# BatteryTemp.net
KiCad netlist of a schematic drawn in EAGLE
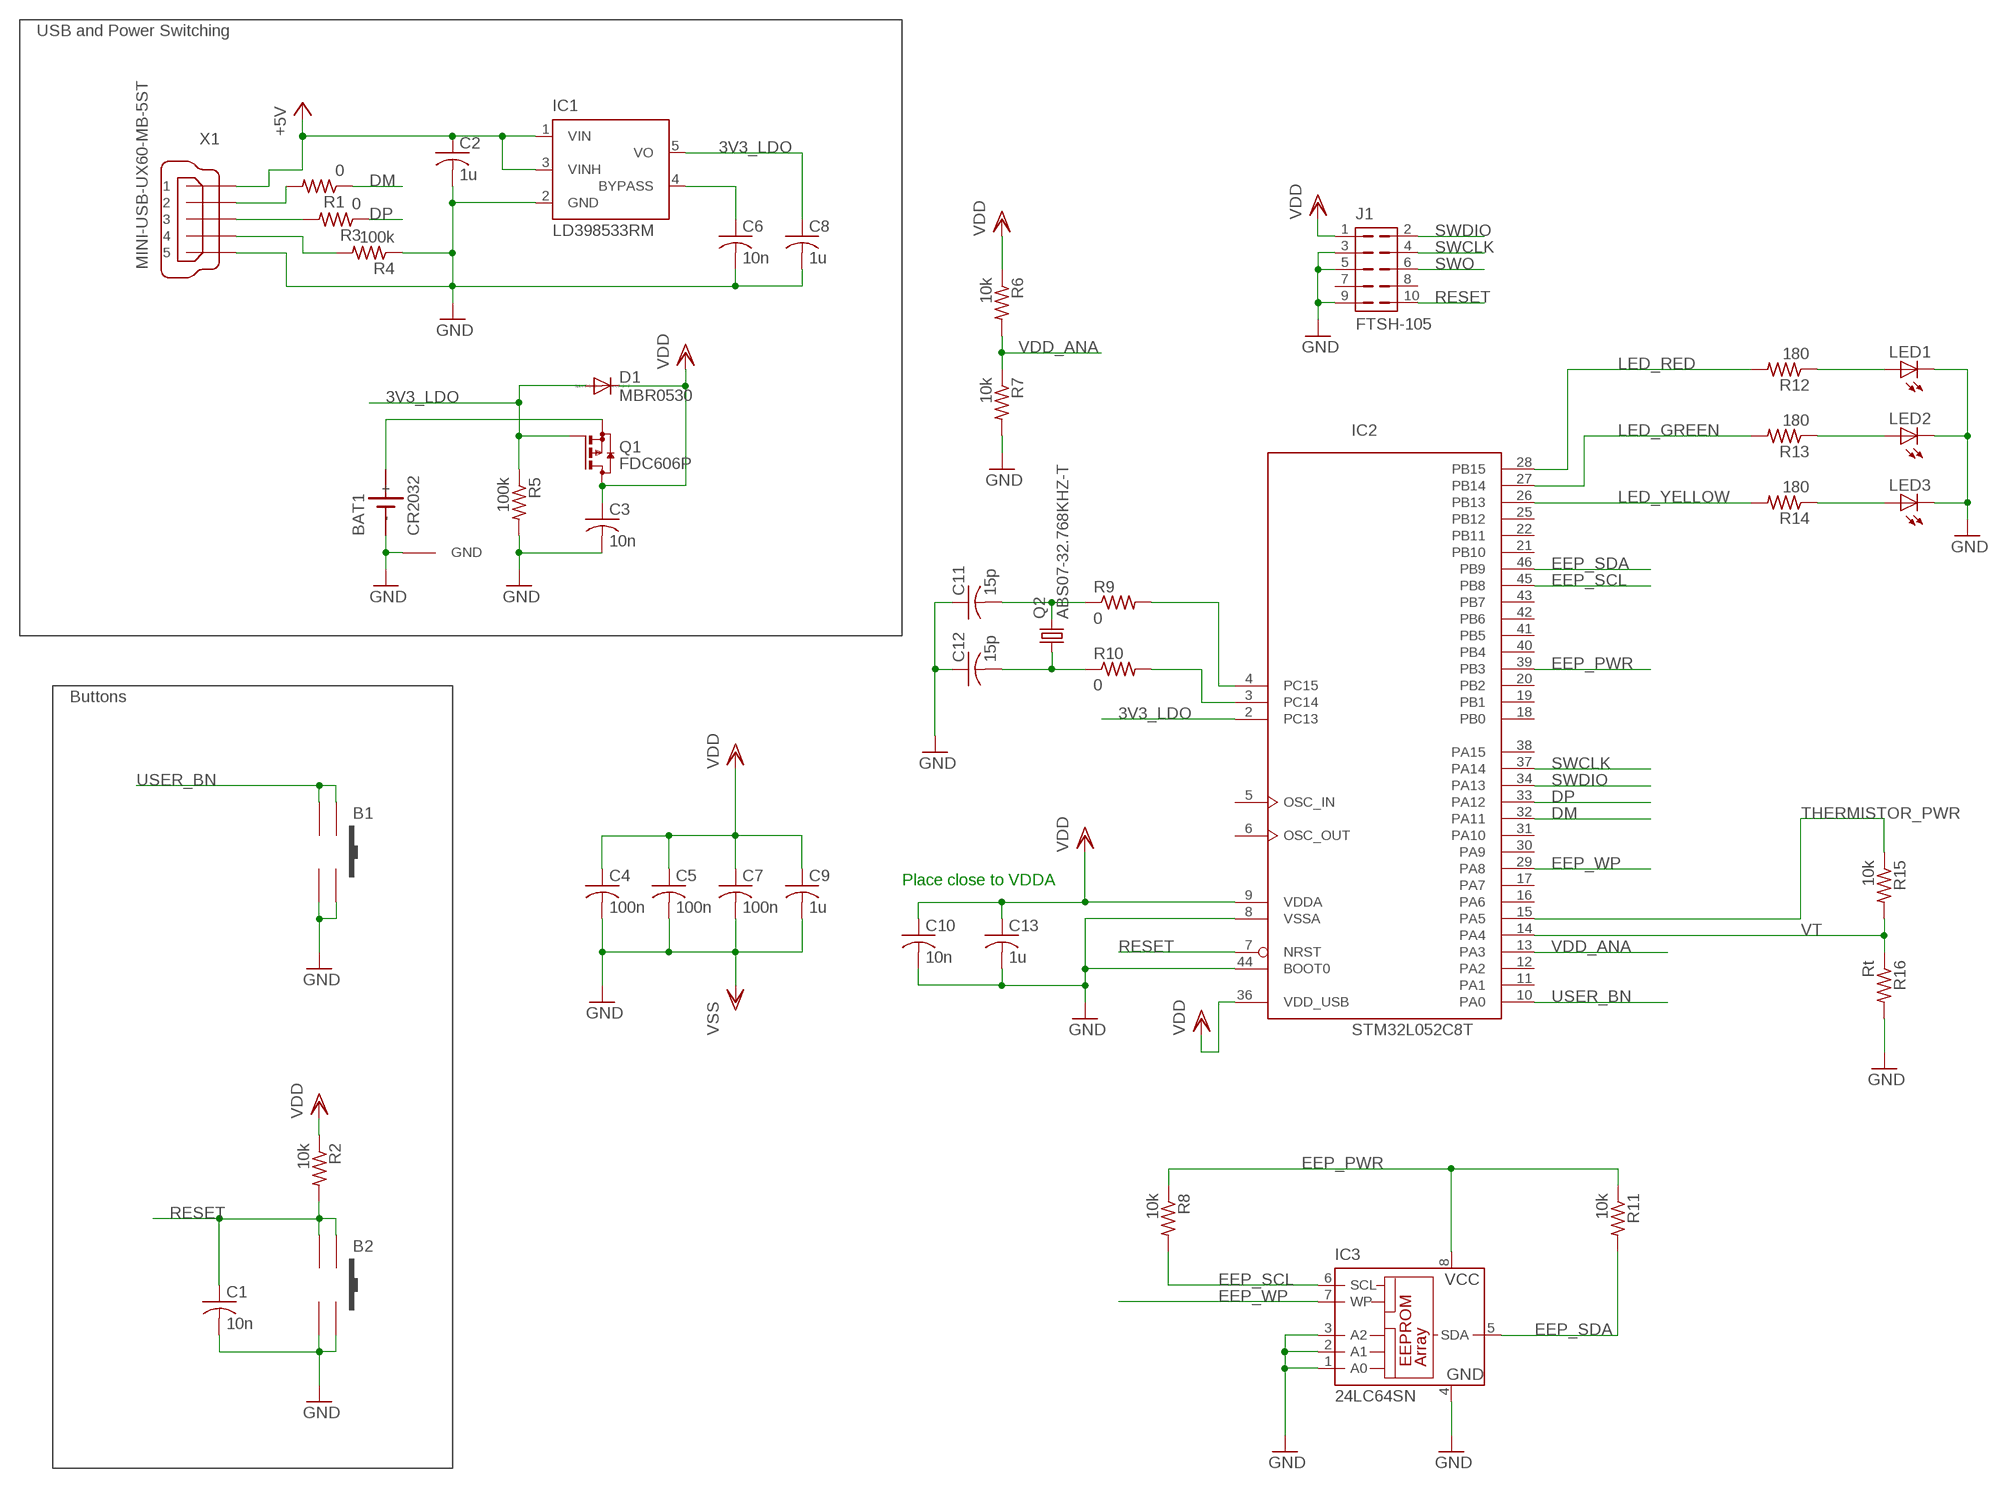
[diagram p0: schematic, sheet 1]

(export (version "E")
  (design (tool "Eeschema 10.0.6"))
  (components
    (comp (ref "B1")
      (value "PTS525SM10SMTR")
      (footprint "eagle-import:PTS525SM10SMTR")
      (libsource (lib "eagle-import") (part "PTS525SM10SMTR"))
    )
    (comp (ref "B2")
      (value "PTS525SM10SMTR")
      (footprint "eagle-import:PTS525SM10SMTR")
      (libsource (lib "eagle-import") (part "PTS525SM10SMTR"))
    )
    (comp (ref "BAT1")
      (value "CR2032")
      (footprint "eagle-import:COIN_CELL")
      (libsource (lib "eagle-import") (part "SN2032"))
    )
    (comp (ref "C1")
      (value "10n")
      (footprint "eagle-import:C0603")
      (libsource (lib "eagle-import") (part "C-USC0603"))
    )
    (comp (ref "C2")
      (value "1u")
      (footprint "eagle-import:C0603")
      (libsource (lib "eagle-import") (part "C-USC0603"))
    )
    (comp (ref "C3")
      (value "10n")
      (footprint "eagle-import:C0603")
      (libsource (lib "eagle-import") (part "C-USC0603"))
    )
    (comp (ref "C4")
      (value "100n")
      (footprint "eagle-import:C0603")
      (libsource (lib "eagle-import") (part "C-USC0603"))
    )
    (comp (ref "C5")
      (value "100n")
      (footprint "eagle-import:C0603")
      (libsource (lib "eagle-import") (part "C-USC0603"))
    )
    (comp (ref "C6")
      (value "10n")
      (footprint "eagle-import:C0603")
      (libsource (lib "eagle-import") (part "C-USC0603"))
    )
    (comp (ref "C7")
      (value "100n")
      (footprint "eagle-import:C0603")
      (libsource (lib "eagle-import") (part "C-USC0603"))
    )
    (comp (ref "C8")
      (value "1u")
      (footprint "eagle-import:C0603")
      (libsource (lib "eagle-import") (part "C-USC0603"))
    )
    (comp (ref "C9")
      (value "1u")
      (footprint "eagle-import:C0603")
      (libsource (lib "eagle-import") (part "C-USC0603"))
    )
    (comp (ref "C10")
      (value "10n")
      (footprint "eagle-import:C0603")
      (libsource (lib "eagle-import") (part "C-USC0603"))
    )
    (comp (ref "C11")
      (value "15p")
      (footprint "eagle-import:C0603")
      (libsource (lib "eagle-import") (part "C-USC0603"))
    )
    (comp (ref "C12")
      (value "15p")
      (footprint "eagle-import:C0603")
      (libsource (lib "eagle-import") (part "C-USC0603"))
    )
    (comp (ref "C13")
      (value "1u")
      (footprint "eagle-import:C0603")
      (libsource (lib "eagle-import") (part "C-USC0603"))
    )
    (comp (ref "D1")
      (value "MBR0530")
      (footprint "eagle-import:SOD-123_MINI-SMA")
      (libsource (lib "eagle-import") (part "CGRM400-G1"))
    )
    (comp (ref "IC1")
      (value "LD398533RM")
      (footprint "eagle-import:SOT23-5L")
      (libsource (lib "eagle-import") (part "LD3985M33R"))
    )
    (comp (ref "IC2")
      (value "STM32L052C8T")
      (footprint "eagle-import:LQFP48")
      (libsource (lib "eagle-import") (part "STM32L052CT8"))
    )
    (comp (ref "IC3")
      (value "24LC64SN")
      (footprint "eagle-import:SO-08")
      (fields (field (name "MF") "MICROCHIP") (field (name "MPN") "24LC64-I/SN"))
      (libsource (lib "eagle-import") (part "24SNLC64"))
    )
    (comp (ref "J1")
      (value "FTSH-105")
      (footprint "eagle-import:FTSH-105-01-XXX-DV-K")
      (libsource (lib "eagle-import") (part "FTSH-105"))
    )
    (comp (ref "LED1")
      (value "LEDCHIP-LED0603")
      (footprint "eagle-import:CHIP-LED0603")
      (libsource (lib "eagle-import") (part "LEDCHIP-LED0603"))
    )
    (comp (ref "LED2")
      (value "LEDCHIP-LED0603")
      (footprint "eagle-import:CHIP-LED0603")
      (libsource (lib "eagle-import") (part "LEDCHIP-LED0603"))
    )
    (comp (ref "LED3")
      (value "LEDCHIP-LED0603")
      (footprint "eagle-import:CHIP-LED0603")
      (libsource (lib "eagle-import") (part "LEDCHIP-LED0603"))
    )
    (comp (ref "Q1")
      (value "FDC606P")
      (footprint "eagle-import:SOT-23-6")
      (libsource (lib "eagle-import") (part "FDC606P"))
    )
    (comp (ref "Q2")
      (value "ABS07-32.768KHZ-T")
      (footprint "eagle-import:2-SMD")
      (libsource (lib "eagle-import") (part "ABS07-32.768KHZ-T"))
    )
    (comp (ref "R1")
      (value "0")
      (footprint "eagle-import:R0603")
      (libsource (lib "eagle-import") (part "R-US_R0603"))
    )
    (comp (ref "R2")
      (value "10k")
      (footprint "eagle-import:R0603")
      (libsource (lib "eagle-import") (part "R-US_R0603"))
    )
    (comp (ref "R3")
      (value "0")
      (footprint "eagle-import:R0603")
      (libsource (lib "eagle-import") (part "R-US_R0603"))
    )
    (comp (ref "R4")
      (value "100k")
      (footprint "eagle-import:R0603")
      (libsource (lib "eagle-import") (part "R-US_R0603"))
    )
    (comp (ref "R5")
      (value "100k")
      (footprint "eagle-import:R0603")
      (libsource (lib "eagle-import") (part "R-US_R0603"))
    )
    (comp (ref "R6")
      (value "10k")
      (footprint "eagle-import:R0603")
      (libsource (lib "eagle-import") (part "R-US_R0603"))
    )
    (comp (ref "R7")
      (value "10k")
      (footprint "eagle-import:R0603")
      (libsource (lib "eagle-import") (part "R-US_R0603"))
    )
    (comp (ref "R8")
      (value "10k")
      (footprint "eagle-import:R0603")
      (libsource (lib "eagle-import") (part "R-US_R0603"))
    )
    (comp (ref "R9")
      (value "0")
      (footprint "eagle-import:R0603")
      (libsource (lib "eagle-import") (part "R-US_R0603"))
    )
    (comp (ref "R10")
      (value "0")
      (footprint "eagle-import:R0603")
      (libsource (lib "eagle-import") (part "R-US_R0603"))
    )
    (comp (ref "R11")
      (value "10k")
      (footprint "eagle-import:R0603")
      (libsource (lib "eagle-import") (part "R-US_R0603"))
    )
    (comp (ref "R12")
      (value "180")
      (footprint "eagle-import:R0603")
      (libsource (lib "eagle-import") (part "R-US_R0603"))
    )
    (comp (ref "R13")
      (value "180")
      (footprint "eagle-import:R0603")
      (libsource (lib "eagle-import") (part "R-US_R0603"))
    )
    (comp (ref "R14")
      (value "180")
      (footprint "eagle-import:R0603")
      (libsource (lib "eagle-import") (part "R-US_R0603"))
    )
    (comp (ref "R15")
      (value "10k")
      (footprint "eagle-import:R0603")
      (libsource (lib "eagle-import") (part "R-US_R0603"))
    )
    (comp (ref "R16")
      (value "Rt")
      (footprint "eagle-import:R0603")
      (libsource (lib "eagle-import") (part "R-US_R0603"))
    )
    (comp (ref "T1")
      (value "GND_LUG")
      (footprint "eagle-import:GND_PAD")
      (libsource (lib "eagle-import") (part "GND_LUG"))
    )
    (comp (ref "X1")
      (value "MINI-USB-UX60-MB-5ST")
      (footprint "eagle-import:UX60-MB-5ST")
      (libsource (lib "eagle-import") (part "MINI-USB-UX60-MB-5ST"))
    )
  )
  (nets
    (net (code "1") (name "+5V") (class "Default")
      (node (ref "C2") (pin "1") (pinfunction "1_1") (pintype "passive"))
      (node (ref "IC1") (pin "1") (pinfunction "VIN_1") (pintype "input"))
      (node (ref "IC1") (pin "3") (pinfunction "VINH_3") (pintype "input"))
      (node (ref "X1") (pin "1") (pinfunction "1_1") (pintype "input"))
    )
    (net (code "2") (name "/3V3_LDO") (class "Default")
      (node (ref "C8") (pin "1") (pinfunction "1_1") (pintype "passive"))
      (node (ref "D1") (pin "A") (pinfunction "A_A") (pintype "passive"))
      (node (ref "IC1") (pin "5") (pinfunction "VO_5") (pintype "output"))
      (node (ref "IC2") (pin "2") (pinfunction "PC13_2") (pintype "bidirectional"))
      (node (ref "Q1") (pin "3") (pinfunction "G_3") (pintype "passive"))
      (node (ref "R5") (pin "1") (pinfunction "1_1") (pintype "passive"))
    )
    (net (code "3") (name "/DM") (class "Default")
      (node (ref "IC2") (pin "32") (pinfunction "PA11_32") (pintype "bidirectional"))
      (node (ref "R1") (pin "1") (pinfunction "1_1") (pintype "passive"))
    )
    (net (code "4") (name "/DP") (class "Default")
      (node (ref "IC2") (pin "33") (pinfunction "PA12_33") (pintype "bidirectional"))
      (node (ref "R3") (pin "1") (pinfunction "1_1") (pintype "passive"))
    )
    (net (code "5") (name "/EEP_PWR") (class "Default")
      (node (ref "IC2") (pin "39") (pinfunction "PB3_39") (pintype "bidirectional"))
      (node (ref "IC3") (pin "8") (pinfunction "VCC_8") (pintype "power_in"))
      (node (ref "R11") (pin "1") (pinfunction "1_1") (pintype "passive"))
      (node (ref "R8") (pin "1") (pinfunction "1_1") (pintype "passive"))
    )
    (net (code "6") (name "/EEP_SCL") (class "Default")
      (node (ref "IC2") (pin "45") (pinfunction "PB8_45") (pintype "bidirectional"))
      (node (ref "IC3") (pin "6") (pinfunction "SCL_6") (pintype "input"))
      (node (ref "R8") (pin "2") (pinfunction "2_2") (pintype "passive"))
    )
    (net (code "7") (name "/EEP_SDA") (class "Default")
      (node (ref "IC2") (pin "46") (pinfunction "PB9_46") (pintype "bidirectional"))
      (node (ref "IC3") (pin "5") (pinfunction "SDA_5") (pintype "bidirectional"))
      (node (ref "R11") (pin "2") (pinfunction "2_2") (pintype "passive"))
    )
    (net (code "8") (name "/EEP_WP") (class "Default")
      (node (ref "IC2") (pin "29") (pinfunction "PA8_29") (pintype "bidirectional"))
      (node (ref "IC3") (pin "7") (pinfunction "WP_7") (pintype "input"))
    )
    (net (code "9") (name "/LED_GREEN") (class "Default")
      (node (ref "IC2") (pin "27") (pinfunction "PB14_27") (pintype "bidirectional"))
      (node (ref "R13") (pin "2") (pinfunction "2_2") (pintype "passive"))
    )
    (net (code "10") (name "/LED_RED") (class "Default")
      (node (ref "IC2") (pin "28") (pinfunction "PB15_28") (pintype "bidirectional"))
      (node (ref "R12") (pin "2") (pinfunction "2_2") (pintype "passive"))
    )
    (net (code "11") (name "/LED_YELLOW") (class "Default")
      (node (ref "IC2") (pin "26") (pinfunction "PB13_26") (pintype "bidirectional"))
      (node (ref "R14") (pin "2") (pinfunction "2_2") (pintype "passive"))
    )
    (net (code "12") (name "/RESET") (class "Default")
      (node (ref "B2") (pin "1") (pinfunction "P1_1") (pintype "bidirectional"))
      (node (ref "B2") (pin "2") (pinfunction "P2_2") (pintype "bidirectional"))
      (node (ref "C1") (pin "1") (pinfunction "1_1") (pintype "passive"))
      (node (ref "IC2") (pin "7") (pinfunction "NRST_7") (pintype "bidirectional"))
      (node (ref "J1") (pin "10") (pinfunction "10_10") (pintype "passive"))
      (node (ref "R2") (pin "2") (pinfunction "2_2") (pintype "passive"))
    )
    (net (code "13") (name "/SWCLK") (class "Default")
      (node (ref "IC2") (pin "37") (pinfunction "PA14_37") (pintype "bidirectional"))
      (node (ref "J1") (pin "4") (pinfunction "4_4") (pintype "passive"))
    )
    (net (code "14") (name "/SWDIO") (class "Default")
      (node (ref "IC2") (pin "34") (pinfunction "PA13_34") (pintype "bidirectional"))
      (node (ref "J1") (pin "2") (pinfunction "2_2") (pintype "passive"))
    )
    (net (code "15") (name "/SWO") (class "Default")
      (node (ref "J1") (pin "6") (pinfunction "6_6") (pintype "passive"))
    )
    (net (code "16") (name "/THERMISTOR_PWR") (class "Default")
      (node (ref "IC2") (pin "15") (pinfunction "PA5_15") (pintype "bidirectional"))
      (node (ref "R15") (pin "1") (pinfunction "1_1") (pintype "passive"))
    )
    (net (code "17") (name "/USER_BN") (class "Default")
      (node (ref "B1") (pin "1") (pinfunction "P1_1") (pintype "bidirectional"))
      (node (ref "B1") (pin "2") (pinfunction "P2_2") (pintype "bidirectional"))
      (node (ref "IC2") (pin "10") (pinfunction "PA0_10") (pintype "bidirectional"))
    )
    (net (code "18") (name "/VDD_ANA") (class "Default")
      (node (ref "IC2") (pin "13") (pinfunction "PA3_13") (pintype "bidirectional"))
      (node (ref "R6") (pin "2") (pinfunction "2_2") (pintype "passive"))
      (node (ref "R7") (pin "1") (pinfunction "1_1") (pintype "passive"))
    )
    (net (code "19") (name "/VT") (class "Default")
      (node (ref "IC2") (pin "14") (pinfunction "PA4_14") (pintype "bidirectional"))
      (node (ref "R15") (pin "2") (pinfunction "2_2") (pintype "passive"))
      (node (ref "R16") (pin "1") (pinfunction "1_1") (pintype "passive"))
    )
    (net (code "20") (name "GND") (class "Default")
      (node (ref "B1") (pin "3") (pinfunction "P3_3") (pintype "bidirectional"))
      (node (ref "B1") (pin "4") (pinfunction "P4_4") (pintype "bidirectional"))
      (node (ref "B2") (pin "3") (pinfunction "P3_3") (pintype "bidirectional"))
      (node (ref "B2") (pin "4") (pinfunction "P4_4") (pintype "bidirectional"))
      (node (ref "BAT1") (pin "GND1") (pinfunction "-_GND1") (pintype "passive"))
      (node (ref "C1") (pin "2") (pinfunction "2_2") (pintype "passive"))
      (node (ref "C10") (pin "2") (pinfunction "2_2") (pintype "passive"))
      (node (ref "C11") (pin "1") (pinfunction "1_1") (pintype "passive"))
      (node (ref "C12") (pin "1") (pinfunction "1_1") (pintype "passive"))
      (node (ref "C13") (pin "2") (pinfunction "2_2") (pintype "passive"))
      (node (ref "C2") (pin "2") (pinfunction "2_2") (pintype "passive"))
      (node (ref "C3") (pin "2") (pinfunction "2_2") (pintype "passive"))
      (node (ref "C4") (pin "2") (pinfunction "2_2") (pintype "passive"))
      (node (ref "C5") (pin "2") (pinfunction "2_2") (pintype "passive"))
      (node (ref "C6") (pin "2") (pinfunction "2_2") (pintype "passive"))
      (node (ref "C7") (pin "2") (pinfunction "2_2") (pintype "passive"))
      (node (ref "C8") (pin "2") (pinfunction "2_2") (pintype "passive"))
      (node (ref "C9") (pin "2") (pinfunction "2_2") (pintype "passive"))
      (node (ref "IC1") (pin "2") (pinfunction "GND_2") (pintype "power_in"))
      (node (ref "IC2") (pin "44") (pinfunction "BOOT0_44") (pintype "input"))
      (node (ref "IC2") (pin "8") (pinfunction "VSSA_8") (pintype "power_in"))
      (node (ref "IC3") (pin "1") (pinfunction "A0_1") (pintype "input"))
      (node (ref "IC3") (pin "2") (pinfunction "A1_2") (pintype "input"))
      (node (ref "IC3") (pin "3") (pinfunction "A2_3") (pintype "input"))
      (node (ref "IC3") (pin "4") (pinfunction "GND_4") (pintype "power_in"))
      (node (ref "J1") (pin "3") (pinfunction "3_3") (pintype "passive"))
      (node (ref "J1") (pin "5") (pinfunction "5_5") (pintype "passive"))
      (node (ref "J1") (pin "9") (pinfunction "9_9") (pintype "passive"))
      (node (ref "LED1") (pin "C") (pinfunction "C_C") (pintype "passive"))
      (node (ref "LED2") (pin "C") (pinfunction "C_C") (pintype "passive"))
      (node (ref "LED3") (pin "C") (pinfunction "C_C") (pintype "passive"))
      (node (ref "R16") (pin "2") (pinfunction "2_2") (pintype "passive"))
      (node (ref "R4") (pin "1") (pinfunction "1_1") (pintype "passive"))
      (node (ref "R5") (pin "2") (pinfunction "2_2") (pintype "passive"))
      (node (ref "R7") (pin "2") (pinfunction "2_2") (pintype "passive"))
      (node (ref "T1") (pin "P$1") (pinfunction "GND_P$1") (pintype "bidirectional"))
      (node (ref "X1") (pin "5") (pinfunction "5_5") (pintype "input"))
    )
    (net (code "21") (name "Net-(IC1-BYPASS)") (class "Default")
      (node (ref "C6") (pin "1") (pinfunction "1_1") (pintype "passive"))
      (node (ref "IC1") (pin "4") (pinfunction "BYPASS_4") (pintype "passive"))
    )
    (net (code "22") (name "Net-(IC2A-PC14)") (class "Default")
      (node (ref "IC2") (pin "3") (pinfunction "PC14_3") (pintype "bidirectional"))
      (node (ref "R10") (pin "2") (pinfunction "2_2") (pintype "passive"))
    )
    (net (code "23") (name "Net-(IC2A-PC15)") (class "Default")
      (node (ref "IC2") (pin "4") (pinfunction "PC15_4") (pintype "bidirectional"))
      (node (ref "R9") (pin "2") (pinfunction "2_2") (pintype "passive"))
    )
    (net (code "24") (name "Net-(LED1-PadA)") (class "Default")
      (node (ref "LED1") (pin "A") (pinfunction "A_A") (pintype "passive"))
      (node (ref "R12") (pin "1") (pinfunction "1_1") (pintype "passive"))
    )
    (net (code "25") (name "Net-(LED2-PadA)") (class "Default")
      (node (ref "LED2") (pin "A") (pinfunction "A_A") (pintype "passive"))
      (node (ref "R13") (pin "1") (pinfunction "1_1") (pintype "passive"))
    )
    (net (code "26") (name "Net-(LED3-PadA)") (class "Default")
      (node (ref "LED3") (pin "A") (pinfunction "A_A") (pintype "passive"))
      (node (ref "R14") (pin "1") (pinfunction "1_1") (pintype "passive"))
    )
    (net (code "27") (name "Net-(Q1-S)") (class "Default")
      (node (ref "BAT1") (pin "VPLUS1") (pinfunction "+_VPLUS1") (pintype "passive"))
      (node (ref "BAT1") (pin "VPLUS2") (pinfunction "+_VPLUS2") (pintype "passive"))
      (node (ref "Q1") (pin "4") (pinfunction "S_4") (pintype "passive"))
    )
    (net (code "28") (name "Net-(Q2-1)") (class "Default")
      (node (ref "C12") (pin "2") (pinfunction "2_2") (pintype "passive"))
      (node (ref "Q2") (pin "P$1") (pinfunction "1_P$1") (pintype "passive"))
      (node (ref "R10") (pin "1") (pinfunction "1_1") (pintype "passive"))
    )
    (net (code "29") (name "Net-(Q2-2)") (class "Default")
      (node (ref "C11") (pin "2") (pinfunction "2_2") (pintype "passive"))
      (node (ref "Q2") (pin "P$2") (pinfunction "2_P$2") (pintype "passive"))
      (node (ref "R9") (pin "1") (pinfunction "1_1") (pintype "passive"))
    )
    (net (code "30") (name "Net-(R1-Pad2)") (class "Default")
      (node (ref "R1") (pin "2") (pinfunction "2_2") (pintype "passive"))
      (node (ref "X1") (pin "2") (pinfunction "2_2") (pintype "input"))
    )
    (net (code "31") (name "Net-(R3-Pad2)") (class "Default")
      (node (ref "R3") (pin "2") (pinfunction "2_2") (pintype "passive"))
      (node (ref "X1") (pin "3") (pinfunction "3_3") (pintype "input"))
    )
    (net (code "32") (name "Net-(R4-Pad2)") (class "Default")
      (node (ref "R4") (pin "2") (pinfunction "2_2") (pintype "passive"))
      (node (ref "X1") (pin "4") (pinfunction "4_4") (pintype "input"))
    )
    (net (code "33") (name "VDD") (class "Default")
      (node (ref "C10") (pin "1") (pinfunction "1_1") (pintype "passive"))
      (node (ref "C13") (pin "1") (pinfunction "1_1") (pintype "passive"))
      (node (ref "C3") (pin "1") (pinfunction "1_1") (pintype "passive"))
      (node (ref "C4") (pin "1") (pinfunction "1_1") (pintype "passive"))
      (node (ref "C5") (pin "1") (pinfunction "1_1") (pintype "passive"))
      (node (ref "C7") (pin "1") (pinfunction "1_1") (pintype "passive"))
      (node (ref "C9") (pin "1") (pinfunction "1_1") (pintype "passive"))
      (node (ref "D1") (pin "C") (pinfunction "C_C") (pintype "passive"))
      (node (ref "IC2") (pin "36") (pinfunction "VDD_USB_36") (pintype "power_in"))
      (node (ref "IC2") (pin "9") (pinfunction "VDDA_9") (pintype "power_in"))
      (node (ref "J1") (pin "1") (pinfunction "1_1") (pintype "passive"))
      (node (ref "Q1") (pin "1") (pinfunction "D_1") (pintype "passive"))
      (node (ref "Q1") (pin "2") (pinfunction "D_2") (pintype "passive"))
      (node (ref "Q1") (pin "5") (pinfunction "D_5") (pintype "passive"))
      (node (ref "Q1") (pin "6") (pinfunction "D_6") (pintype "passive"))
      (node (ref "R2") (pin "1") (pinfunction "1_1") (pintype "passive"))
      (node (ref "R6") (pin "1") (pinfunction "1_1") (pintype "passive"))
    )
    (net (code "34") (name "unconnected-(IC2A-OSC_IN-Pad5)") (class "Default")
      (node (ref "IC2") (pin "5") (pinfunction "OSC_IN_5") (pintype "bidirectional"))
    )
    (net (code "35") (name "unconnected-(IC2A-OSC_OUT-Pad6)") (class "Default")
      (node (ref "IC2") (pin "6") (pinfunction "OSC_OUT_6") (pintype "bidirectional"))
    )
    (net (code "36") (name "unconnected-(IC2A-PA1-Pad11)") (class "Default")
      (node (ref "IC2") (pin "11") (pinfunction "PA1_11") (pintype "bidirectional"))
    )
    (net (code "37") (name "unconnected-(IC2A-PA2-Pad12)") (class "Default")
      (node (ref "IC2") (pin "12") (pinfunction "PA2_12") (pintype "bidirectional"))
    )
    (net (code "38") (name "unconnected-(IC2A-PA6-Pad16)") (class "Default")
      (node (ref "IC2") (pin "16") (pinfunction "PA6_16") (pintype "bidirectional"))
    )
    (net (code "39") (name "unconnected-(IC2A-PA7-Pad17)") (class "Default")
      (node (ref "IC2") (pin "17") (pinfunction "PA7_17") (pintype "bidirectional"))
    )
    (net (code "40") (name "unconnected-(IC2A-PA9-Pad30)") (class "Default")
      (node (ref "IC2") (pin "30") (pinfunction "PA9_30") (pintype "bidirectional"))
    )
    (net (code "41") (name "unconnected-(IC2A-PA10-Pad31)") (class "Default")
      (node (ref "IC2") (pin "31") (pinfunction "PA10_31") (pintype "bidirectional"))
    )
    (net (code "42") (name "unconnected-(IC2A-PA15-Pad38)") (class "Default")
      (node (ref "IC2") (pin "38") (pinfunction "PA15_38") (pintype "bidirectional"))
    )
    (net (code "43") (name "unconnected-(IC2A-PB0-Pad18)") (class "Default")
      (node (ref "IC2") (pin "18") (pinfunction "PB0_18") (pintype "bidirectional"))
    )
    (net (code "44") (name "unconnected-(IC2A-PB1-Pad19)") (class "Default")
      (node (ref "IC2") (pin "19") (pinfunction "PB1_19") (pintype "bidirectional"))
    )
    (net (code "45") (name "unconnected-(IC2A-PB2-Pad20)") (class "Default")
      (node (ref "IC2") (pin "20") (pinfunction "PB2_20") (pintype "bidirectional"))
    )
    (net (code "46") (name "unconnected-(IC2A-PB4-Pad40)") (class "Default")
      (node (ref "IC2") (pin "40") (pinfunction "PB4_40") (pintype "bidirectional"))
    )
    (net (code "47") (name "unconnected-(IC2A-PB5-Pad41)") (class "Default")
      (node (ref "IC2") (pin "41") (pinfunction "PB5_41") (pintype "bidirectional"))
    )
    (net (code "48") (name "unconnected-(IC2A-PB6-Pad42)") (class "Default")
      (node (ref "IC2") (pin "42") (pinfunction "PB6_42") (pintype "bidirectional"))
    )
    (net (code "49") (name "unconnected-(IC2A-PB7-Pad43)") (class "Default")
      (node (ref "IC2") (pin "43") (pinfunction "PB7_43") (pintype "bidirectional"))
    )
    (net (code "50") (name "unconnected-(IC2A-PB10-Pad21)") (class "Default")
      (node (ref "IC2") (pin "21") (pinfunction "PB10_21") (pintype "bidirectional"))
    )
    (net (code "51") (name "unconnected-(IC2A-PB11-Pad22)") (class "Default")
      (node (ref "IC2") (pin "22") (pinfunction "PB11_22") (pintype "bidirectional"))
    )
    (net (code "52") (name "unconnected-(IC2A-PB12-Pad25)") (class "Default")
      (node (ref "IC2") (pin "25") (pinfunction "PB12_25") (pintype "bidirectional"))
    )
    (net (code "53") (name "unconnected-(J1-Pad7)") (class "Default")
      (node (ref "J1") (pin "7") (pinfunction "7_7") (pintype "passive"))
    )
    (net (code "54") (name "unconnected-(J1-Pad8)") (class "Default")
      (node (ref "J1") (pin "8") (pinfunction "8_8") (pintype "passive"))
    )
  )
)
